# ConnectionMCU.net
KiCad netlist of a schematic drawn in Altium Designer
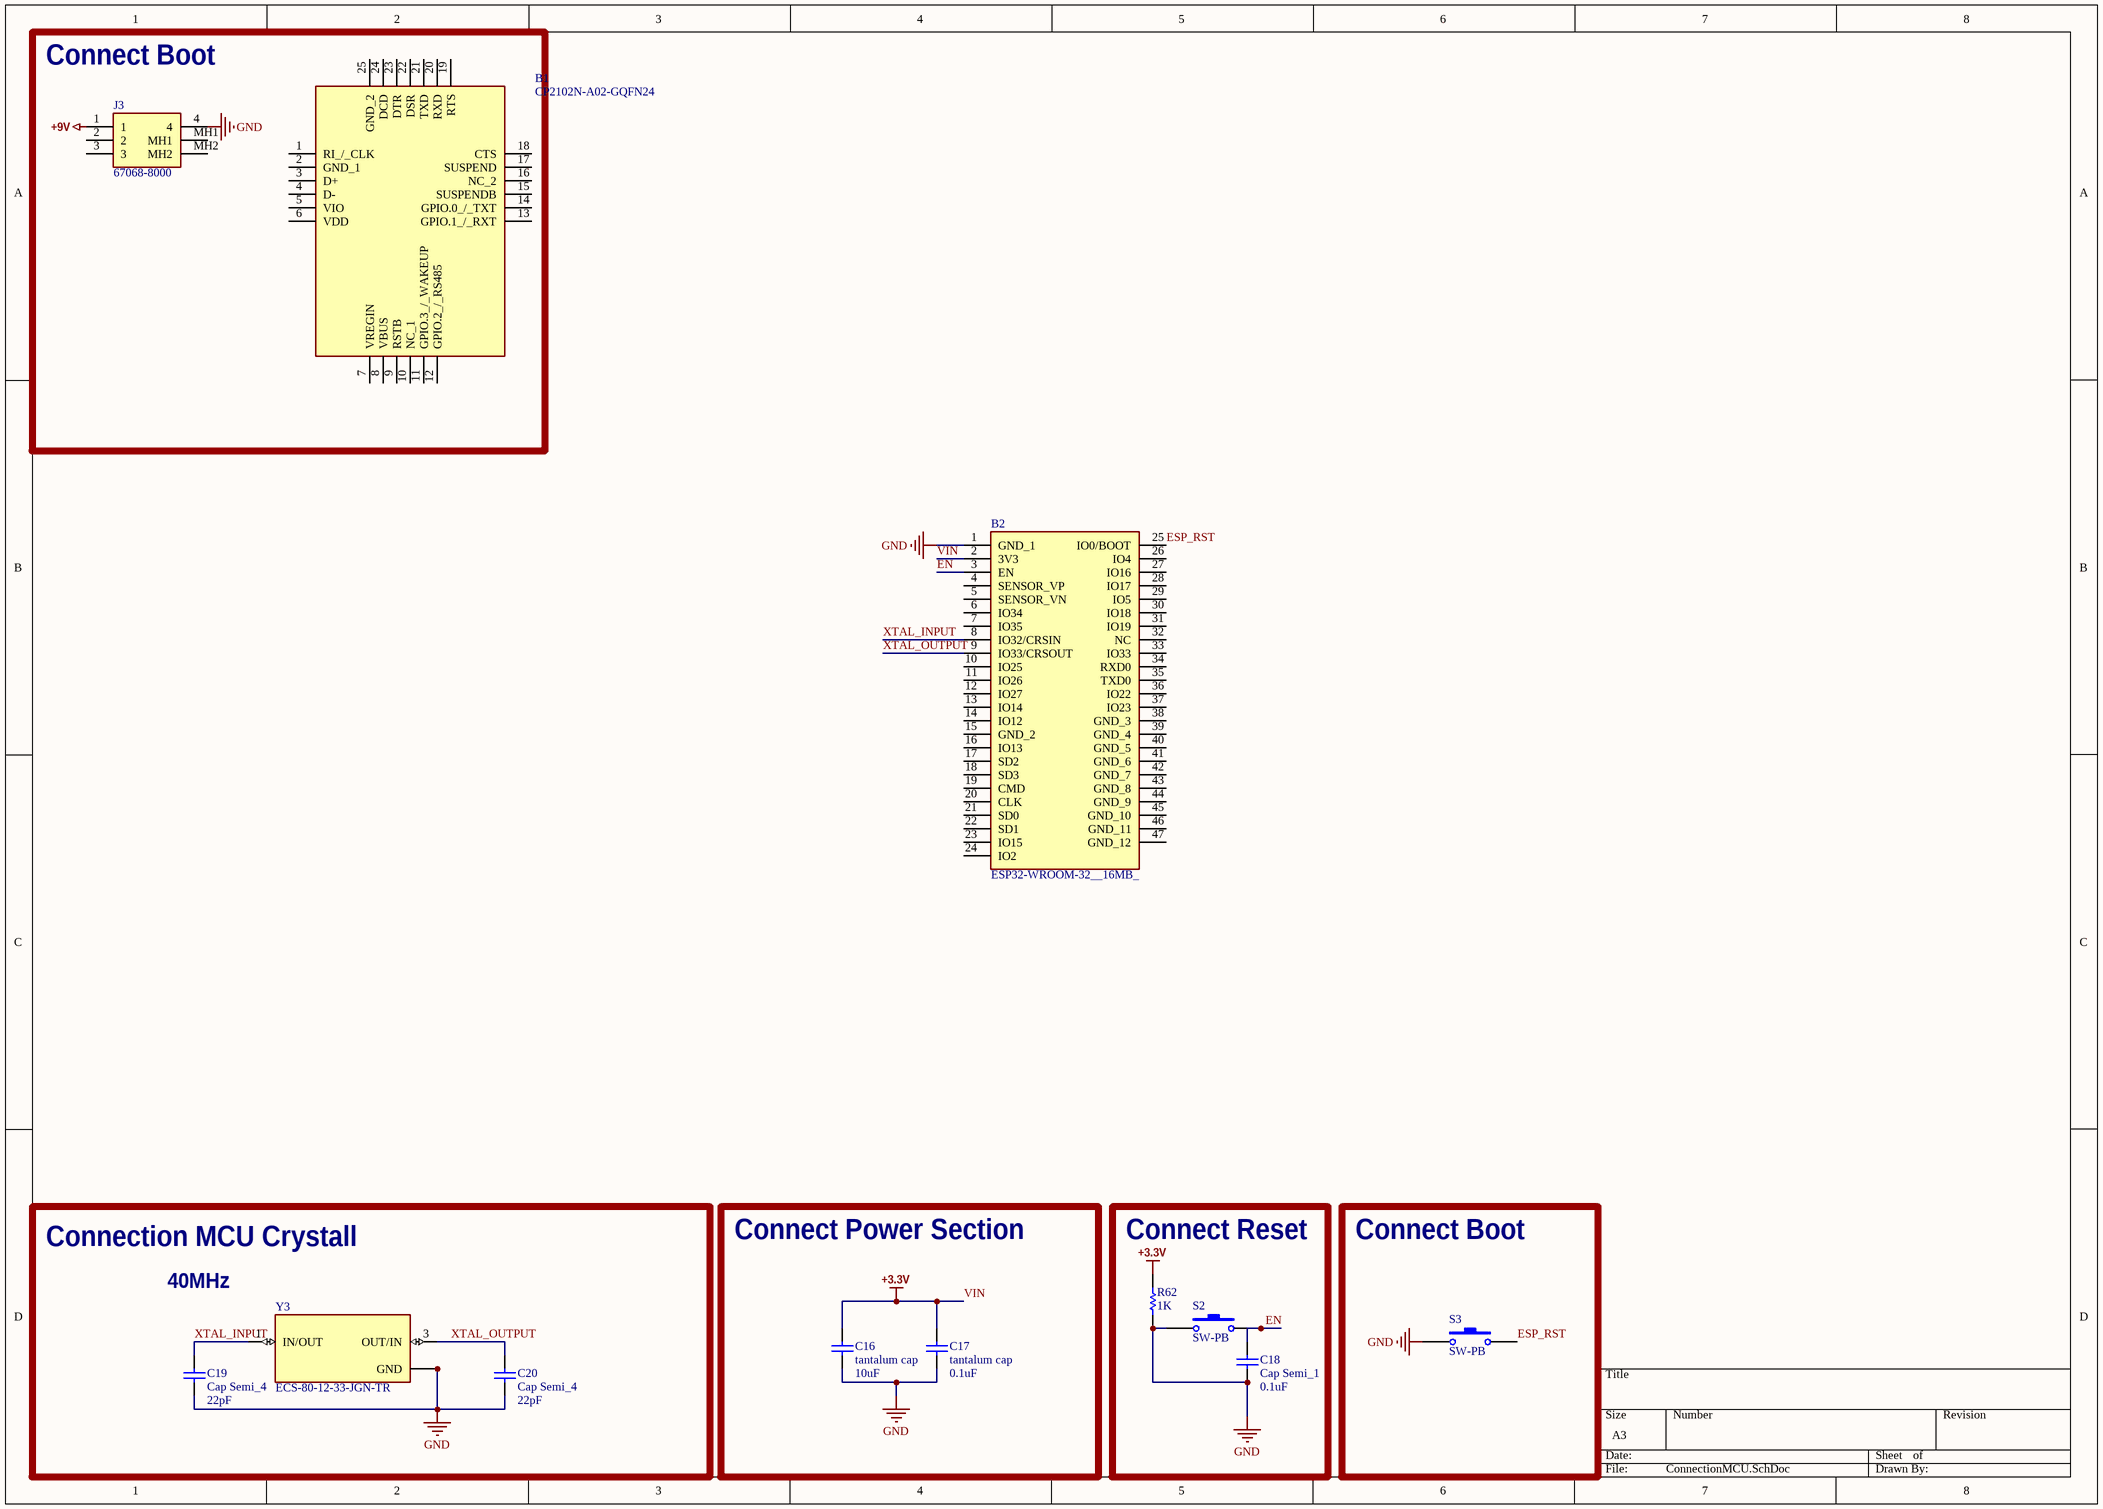
[diagram p0: ConnectionMCU.SchDoc]

(export (version "E")
  (design (tool "Eeschema 10.0.6"))
  (components
    (comp (ref "B1")
      (value "CP2102N-A02-GQFN24")
      (footprint "QFN50P400X400X80-25N-D")
      (description "USB Interface IC USB to UART bridge - QFN24")
      (fields (field (name "MOUSER PART NUMBER") "634-CP2102NA02GQFN24"))
      (libsource (lib "Integrated_Library1") (part "CP2102N-A02-GQFN24"))
    )
    (comp (ref "B2")
      (value "ESP32-WROOM-32__16MB_")
      (footprint "ESP32WROOM3216MB")
      (description "WiFi Modules (802.11)")
      (fields
        (field (name "MANUFACTURER_PART_NUMBER") "ESP32-WROOM-32 (16MB)")
        (field (name "MOUSER PART NUMBER") "356-ESPWROOM3216MB")
      )
      (libsource (lib "Integrated_Library1") (part "ESP32-WROOM-32__16MB_"))
    )
    (comp (ref "C16")
      (value "tantalum cap")
      (footprint "C1206tancap")
      (description "Capacitor (Semiconductor SIM Model)")
      (fields (field (name "ALTIUM_VALUE") "10uF") (field (name "PUBLISHER") "Altium Limited"))
      (libsource (lib "smartmcu") (part "Cap Semi_6"))
    )
    (comp (ref "C17")
      (value "tantalum cap")
      (footprint "C1206tancap")
      (description "Capacitor (Semiconductor SIM Model)")
      (fields (field (name "ALTIUM_VALUE") "0.1uF") (field (name "PUBLISHER") "Altium Limited"))
      (libsource (lib "smartmcu") (part "Cap Semi_6"))
    )
    (comp (ref "C18")
      (value "Cap Semi_1")
      (footprint "1608[0603]cap")
      (description "Capacitor (Semiconductor SIM Model)")
      (fields (field (name "ALTIUM_VALUE") "0.1uF") (field (name "PUBLISHER") "Altium Limited"))
      (libsource (lib "smartmcu") (part "Cap Semi_1"))
    )
    (comp (ref "C19")
      (value "Cap Semi_4")
      (footprint "0402cap")
      (description "Capacitor (Semiconductor SIM Model)")
      (fields (field (name "ALTIUM_VALUE") "22pF") (field (name "PUBLISHER") "Altium Limited"))
      (libsource (lib "smartmcu") (part "Cap Semi_4"))
    )
    (comp (ref "C20")
      (value "Cap Semi_4")
      (footprint "0402cap")
      (description "Capacitor (Semiconductor SIM Model)")
      (fields (field (name "ALTIUM_VALUE") "22pF") (field (name "PUBLISHER") "Altium Limited"))
      (libsource (lib "smartmcu") (part "Cap Semi_4"))
    )
    (comp (ref "J3")
      (value "67068-8000")
      (footprint "670688000")
      (description "USB Connectors USB TYPE B RECEPT. Rt.Angle Gold Flash")
      (fields (field (name "MOUSER PART NUMBER") "538-67068-8000"))
      (libsource (lib "Integrated_Library1") (part "67068-8000"))
    )
    (comp (ref "R62")
      (value "1K")
      (footprint "MY_0603")
      (description "Standard resistor")
      (fields (field (name "ASID PART NUMBER") "Res-AS"))
      (libsource (lib "Mylib+Rev+4") (part "Res"))
    )
    (comp (ref "S2")
      (value "SW-PB")
      (footprint "SPST-2_body")
      (description "Switch")
      (fields (field (name "PUBLISHER") "Altium Limited"))
      (libsource (lib "smartmcu") (part "SW-PB"))
    )
    (comp (ref "S3")
      (value "SW-PB")
      (footprint "SPST-2_body")
      (description "Switch")
      (fields (field (name "PUBLISHER") "Altium Limited"))
      (libsource (lib "smartmcu") (part "SW-PB"))
    )
    (comp (ref "Y3")
      (value "ECS-80-12-33-JGN-TR")
      (footprint "8MHZCrystall")
      (description "8MHz Â±20ppm Crystal 12pF 400 Ohms 4-SMD, No Lead")
      (fields
        (field (name "MF") "ECS Inc.")
        (field (name "BUYPART") "https://www.snapeda.com/parts/ECS-80-12-33-JGN-TR/ECS%20Inc./view-part/4477300/?ref=eda")
      )
      (libsource (lib "smartmcu") (part "ECS-80-12-33-JGN-TR"))
    )
  )
  (nets
    (net (code "1") (name "+3.3V") (class "Default")
      (node (ref "B2") (pin "2") (pinfunction "3V3_2") (pintype "passive"))
      (node (ref "C16") (pin "2") (pinfunction "2_2") (pintype "passive"))
      (node (ref "C17") (pin "2") (pinfunction "2_2") (pintype "passive"))
      (node (ref "R62") (pin "2") (pinfunction "2_2") (pintype "passive"))
    )
    (net (code "2") (name "+9V") (class "Default")
      (node (ref "J3") (pin "1") (pinfunction "1_1") (pintype "passive"))
    )
    (net (code "3") (name "/EN") (class "Default")
      (node (ref "B2") (pin "3") (pinfunction "EN_3") (pintype "passive"))
      (node (ref "C18") (pin "2") (pinfunction "2_2") (pintype "passive"))
      (node (ref "S2") (pin "2") (pinfunction "2_2") (pintype "passive"))
    )
    (net (code "4") (name "/ESP_RST") (class "Default")
      (node (ref "B2") (pin "25") (pinfunction "IO0/BOOT_25") (pintype "passive"))
      (node (ref "S3") (pin "2") (pinfunction "2_2") (pintype "passive"))
    )
    (net (code "5") (name "/XTAL_INPUT") (class "Default")
      (node (ref "B2") (pin "8") (pinfunction "IO32/CRSIN_8") (pintype "passive"))
      (node (ref "C19") (pin "2") (pinfunction "2_2") (pintype "passive"))
      (node (ref "Y3") (pin "1") (pinfunction "IN/OUT_1") (pintype "bidirectional"))
    )
    (net (code "6") (name "/XTAL_OUTPUT") (class "Default")
      (node (ref "B2") (pin "9") (pinfunction "IO33/CRSOUT_9") (pintype "passive"))
      (node (ref "C20") (pin "2") (pinfunction "2_2") (pintype "passive"))
      (node (ref "Y3") (pin "3") (pinfunction "OUT/IN_3") (pintype "bidirectional"))
    )
    (net (code "7") (name "GND") (class "Default")
      (node (ref "B2") (pin "1") (pinfunction "GND_1_1") (pintype "passive"))
      (node (ref "C16") (pin "1") (pinfunction "1_1") (pintype "passive"))
      (node (ref "C17") (pin "1") (pinfunction "1_1") (pintype "passive"))
      (node (ref "C18") (pin "1") (pinfunction "1_1") (pintype "passive"))
      (node (ref "C19") (pin "1") (pinfunction "1_1") (pintype "passive"))
      (node (ref "C20") (pin "1") (pinfunction "1_1") (pintype "passive"))
      (node (ref "J3") (pin "4") (pinfunction "4_4") (pintype "passive"))
      (node (ref "R62") (pin "1") (pinfunction "1_1") (pintype "passive"))
      (node (ref "S2") (pin "1") (pinfunction "1_1") (pintype "passive"))
      (node (ref "S3") (pin "1") (pinfunction "1_1") (pintype "passive"))
      (node (ref "Y3") (pin "2") (pinfunction "GND_2") (pintype "power_in"))
      (node (ref "Y3") (pin "4") (pinfunction "GND_4") (pintype "power_in"))
    )
    (net (code "8") (name "unconnected-(B1-CTS-Pad18)") (class "Default")
      (node (ref "B1") (pin "18") (pinfunction "CTS_18") (pintype "passive"))
    )
    (net (code "9") (name "unconnected-(B1-D+-Pad3)") (class "Default")
      (node (ref "B1") (pin "3") (pinfunction "D+_3") (pintype "passive"))
    )
    (net (code "10") (name "unconnected-(B1-D--Pad4)") (class "Default")
      (node (ref "B1") (pin "4") (pinfunction "D-_4") (pintype "passive"))
    )
    (net (code "11") (name "unconnected-(B1-DCD-Pad24)") (class "Default")
      (node (ref "B1") (pin "24") (pinfunction "DCD_24") (pintype "passive"))
    )
    (net (code "12") (name "unconnected-(B1-DSR-Pad22)") (class "Default")
      (node (ref "B1") (pin "22") (pinfunction "DSR_22") (pintype "passive"))
    )
    (net (code "13") (name "unconnected-(B1-DTR-Pad23)") (class "Default")
      (node (ref "B1") (pin "23") (pinfunction "DTR_23") (pintype "passive"))
    )
    (net (code "14") (name "unconnected-(B1-GND_1-Pad2)") (class "Default")
      (node (ref "B1") (pin "2") (pinfunction "GND_1_2") (pintype "passive"))
    )
    (net (code "15") (name "unconnected-(B1-GND_2-Pad25)") (class "Default")
      (node (ref "B1") (pin "25") (pinfunction "GND_2_25") (pintype "passive"))
    )
    (net (code "16") (name "unconnected-(B1-GPIO.0_{slash}_TXT-Pad14)") (class "Default")
      (node (ref "B1") (pin "14") (pinfunction "GPIO.0_/_TXT_14") (pintype "passive"))
    )
    (net (code "17") (name "unconnected-(B1-GPIO.1_{slash}_RXT-Pad13)") (class "Default")
      (node (ref "B1") (pin "13") (pinfunction "GPIO.1_/_RXT_13") (pintype "passive"))
    )
    (net (code "18") (name "unconnected-(B1-GPIO.2_{slash}_RS485-Pad12)") (class "Default")
      (node (ref "B1") (pin "12") (pinfunction "GPIO.2_/_RS485_12") (pintype "passive"))
    )
    (net (code "19") (name "unconnected-(B1-GPIO.3_{slash}_WAKEUP-Pad11)") (class "Default")
      (node (ref "B1") (pin "11") (pinfunction "GPIO.3_/_WAKEUP_11") (pintype "passive"))
    )
    (net (code "20") (name "unconnected-(B1-NC_1-Pad10)") (class "Default")
      (node (ref "B1") (pin "10") (pinfunction "NC_1_10") (pintype "passive"))
    )
    (net (code "21") (name "unconnected-(B1-NC_2-Pad16)") (class "Default")
      (node (ref "B1") (pin "16") (pinfunction "NC_2_16") (pintype "passive"))
    )
    (net (code "22") (name "unconnected-(B1-RI_{slash}_CLK-Pad1)") (class "Default")
      (node (ref "B1") (pin "1") (pinfunction "RI_/_CLK_1") (pintype "passive"))
    )
    (net (code "23") (name "unconnected-(B1-RSTB-Pad9)") (class "Default")
      (node (ref "B1") (pin "9") (pinfunction "RSTB_9") (pintype "passive"))
    )
    (net (code "24") (name "unconnected-(B1-RTS-Pad19)") (class "Default")
      (node (ref "B1") (pin "19") (pinfunction "RTS_19") (pintype "passive"))
    )
    (net (code "25") (name "unconnected-(B1-RXD-Pad20)") (class "Default")
      (node (ref "B1") (pin "20") (pinfunction "RXD_20") (pintype "passive"))
    )
    (net (code "26") (name "unconnected-(B1-SUSPEND-Pad17)") (class "Default")
      (node (ref "B1") (pin "17") (pinfunction "SUSPEND_17") (pintype "passive"))
    )
    (net (code "27") (name "unconnected-(B1-SUSPENDB-Pad15)") (class "Default")
      (node (ref "B1") (pin "15") (pinfunction "SUSPENDB_15") (pintype "passive"))
    )
    (net (code "28") (name "unconnected-(B1-TXD-Pad21)") (class "Default")
      (node (ref "B1") (pin "21") (pinfunction "TXD_21") (pintype "passive"))
    )
    (net (code "29") (name "unconnected-(B1-VBUS-Pad8)") (class "Default")
      (node (ref "B1") (pin "8") (pinfunction "VBUS_8") (pintype "passive"))
    )
    (net (code "30") (name "unconnected-(B1-VDD-Pad6)") (class "Default")
      (node (ref "B1") (pin "6") (pinfunction "VDD_6") (pintype "passive"))
    )
    (net (code "31") (name "unconnected-(B1-VIO-Pad5)") (class "Default")
      (node (ref "B1") (pin "5") (pinfunction "VIO_5") (pintype "passive"))
    )
    (net (code "32") (name "unconnected-(B1-VREGIN-Pad7)") (class "Default")
      (node (ref "B1") (pin "7") (pinfunction "VREGIN_7") (pintype "passive"))
    )
    (net (code "33") (name "unconnected-(B2-CLK-Pad20)") (class "Default")
      (node (ref "B2") (pin "20") (pinfunction "CLK_20") (pintype "passive"))
    )
    (net (code "34") (name "unconnected-(B2-CMD-Pad19)") (class "Default")
      (node (ref "B2") (pin "19") (pinfunction "CMD_19") (pintype "passive"))
    )
    (net (code "35") (name "unconnected-(B2-GND_2-Pad15)") (class "Default")
      (node (ref "B2") (pin "15") (pinfunction "GND_2_15") (pintype "passive"))
    )
    (net (code "36") (name "unconnected-(B2-GND_3-Pad38)") (class "Default")
      (node (ref "B2") (pin "38") (pinfunction "GND_3_38") (pintype "passive"))
    )
    (net (code "37") (name "unconnected-(B2-GND_4-Pad39)") (class "Default")
      (node (ref "B2") (pin "39") (pinfunction "GND_4_39") (pintype "passive"))
    )
    (net (code "38") (name "unconnected-(B2-GND_5-Pad40)") (class "Default")
      (node (ref "B2") (pin "40") (pinfunction "GND_5_40") (pintype "passive"))
    )
    (net (code "39") (name "unconnected-(B2-GND_6-Pad41)") (class "Default")
      (node (ref "B2") (pin "41") (pinfunction "GND_6_41") (pintype "passive"))
    )
    (net (code "40") (name "unconnected-(B2-GND_7-Pad42)") (class "Default")
      (node (ref "B2") (pin "42") (pinfunction "GND_7_42") (pintype "passive"))
    )
    (net (code "41") (name "unconnected-(B2-GND_8-Pad43)") (class "Default")
      (node (ref "B2") (pin "43") (pinfunction "GND_8_43") (pintype "passive"))
    )
    (net (code "42") (name "unconnected-(B2-GND_9-Pad44)") (class "Default")
      (node (ref "B2") (pin "44") (pinfunction "GND_9_44") (pintype "passive"))
    )
    (net (code "43") (name "unconnected-(B2-GND_10-Pad45)") (class "Default")
      (node (ref "B2") (pin "45") (pinfunction "GND_10_45") (pintype "passive"))
    )
    (net (code "44") (name "unconnected-(B2-GND_11-Pad46)") (class "Default")
      (node (ref "B2") (pin "46") (pinfunction "GND_11_46") (pintype "passive"))
    )
    (net (code "45") (name "unconnected-(B2-GND_12-Pad47)") (class "Default")
      (node (ref "B2") (pin "47") (pinfunction "GND_12_47") (pintype "passive"))
    )
    (net (code "46") (name "unconnected-(B2-IO2-Pad24)") (class "Default")
      (node (ref "B2") (pin "24") (pinfunction "IO2_24") (pintype "passive"))
    )
    (net (code "47") (name "unconnected-(B2-IO4-Pad26)") (class "Default")
      (node (ref "B2") (pin "26") (pinfunction "IO4_26") (pintype "passive"))
    )
    (net (code "48") (name "unconnected-(B2-IO5-Pad29)") (class "Default")
      (node (ref "B2") (pin "29") (pinfunction "IO5_29") (pintype "passive"))
    )
    (net (code "49") (name "unconnected-(B2-IO12-Pad14)") (class "Default")
      (node (ref "B2") (pin "14") (pinfunction "IO12_14") (pintype "passive"))
    )
    (net (code "50") (name "unconnected-(B2-IO13-Pad16)") (class "Default")
      (node (ref "B2") (pin "16") (pinfunction "IO13_16") (pintype "passive"))
    )
    (net (code "51") (name "unconnected-(B2-IO14-Pad13)") (class "Default")
      (node (ref "B2") (pin "13") (pinfunction "IO14_13") (pintype "passive"))
    )
    (net (code "52") (name "unconnected-(B2-IO15-Pad23)") (class "Default")
      (node (ref "B2") (pin "23") (pinfunction "IO15_23") (pintype "passive"))
    )
    (net (code "53") (name "unconnected-(B2-IO16-Pad27)") (class "Default")
      (node (ref "B2") (pin "27") (pinfunction "IO16_27") (pintype "passive"))
    )
    (net (code "54") (name "unconnected-(B2-IO17-Pad28)") (class "Default")
      (node (ref "B2") (pin "28") (pinfunction "IO17_28") (pintype "passive"))
    )
    (net (code "55") (name "unconnected-(B2-IO18-Pad30)") (class "Default")
      (node (ref "B2") (pin "30") (pinfunction "IO18_30") (pintype "passive"))
    )
    (net (code "56") (name "unconnected-(B2-IO19-Pad31)") (class "Default")
      (node (ref "B2") (pin "31") (pinfunction "IO19_31") (pintype "passive"))
    )
    (net (code "57") (name "unconnected-(B2-IO22-Pad36)") (class "Default")
      (node (ref "B2") (pin "36") (pinfunction "IO22_36") (pintype "passive"))
    )
    (net (code "58") (name "unconnected-(B2-IO23-Pad37)") (class "Default")
      (node (ref "B2") (pin "37") (pinfunction "IO23_37") (pintype "passive"))
    )
    (net (code "59") (name "unconnected-(B2-IO25-Pad10)") (class "Default")
      (node (ref "B2") (pin "10") (pinfunction "IO25_10") (pintype "passive"))
    )
    (net (code "60") (name "unconnected-(B2-IO26-Pad11)") (class "Default")
      (node (ref "B2") (pin "11") (pinfunction "IO26_11") (pintype "passive"))
    )
    (net (code "61") (name "unconnected-(B2-IO27-Pad12)") (class "Default")
      (node (ref "B2") (pin "12") (pinfunction "IO27_12") (pintype "passive"))
    )
    (net (code "62") (name "unconnected-(B2-IO33-Pad33)") (class "Default")
      (node (ref "B2") (pin "33") (pinfunction "IO33_33") (pintype "passive"))
    )
    (net (code "63") (name "unconnected-(B2-IO34-Pad6)") (class "Default")
      (node (ref "B2") (pin "6") (pinfunction "IO34_6") (pintype "passive"))
    )
    (net (code "64") (name "unconnected-(B2-IO35-Pad7)") (class "Default")
      (node (ref "B2") (pin "7") (pinfunction "IO35_7") (pintype "passive"))
    )
    (net (code "65") (name "unconnected-(B2-NC-Pad32)") (class "Default")
      (node (ref "B2") (pin "32") (pinfunction "NC_32") (pintype "passive"))
    )
    (net (code "66") (name "unconnected-(B2-RXD0-Pad34)") (class "Default")
      (node (ref "B2") (pin "34") (pinfunction "RXD0_34") (pintype "passive"))
    )
    (net (code "67") (name "unconnected-(B2-SD0-Pad21)") (class "Default")
      (node (ref "B2") (pin "21") (pinfunction "SD0_21") (pintype "passive"))
    )
    (net (code "68") (name "unconnected-(B2-SD1-Pad22)") (class "Default")
      (node (ref "B2") (pin "22") (pinfunction "SD1_22") (pintype "passive"))
    )
    (net (code "69") (name "unconnected-(B2-SD2-Pad17)") (class "Default")
      (node (ref "B2") (pin "17") (pinfunction "SD2_17") (pintype "passive"))
    )
    (net (code "70") (name "unconnected-(B2-SD3-Pad18)") (class "Default")
      (node (ref "B2") (pin "18") (pinfunction "SD3_18") (pintype "passive"))
    )
    (net (code "71") (name "unconnected-(B2-SENSOR_VN-Pad5)") (class "Default")
      (node (ref "B2") (pin "5") (pinfunction "SENSOR_VN_5") (pintype "passive"))
    )
    (net (code "72") (name "unconnected-(B2-SENSOR_VP-Pad4)") (class "Default")
      (node (ref "B2") (pin "4") (pinfunction "SENSOR_VP_4") (pintype "passive"))
    )
    (net (code "73") (name "unconnected-(B2-TXD0-Pad35)") (class "Default")
      (node (ref "B2") (pin "35") (pinfunction "TXD0_35") (pintype "passive"))
    )
    (net (code "74") (name "unconnected-(J3-Pad2)") (class "Default")
      (node (ref "J3") (pin "2") (pinfunction "2_2") (pintype "passive"))
    )
    (net (code "75") (name "unconnected-(J3-Pad3)") (class "Default")
      (node (ref "J3") (pin "3") (pinfunction "3_3") (pintype "passive"))
    )
    (net (code "76") (name "unconnected-(J3-PadMH1)") (class "Default")
      (node (ref "J3") (pin "MH1") (pinfunction "MH1_MH1") (pintype "passive"))
    )
    (net (code "77") (name "unconnected-(J3-PadMH2)") (class "Default")
      (node (ref "J3") (pin "MH2") (pinfunction "MH2_MH2") (pintype "passive"))
    )
  )
)
